# ensearrosage_2.net
KiCad netlist of a schematic drawn in EAGLE
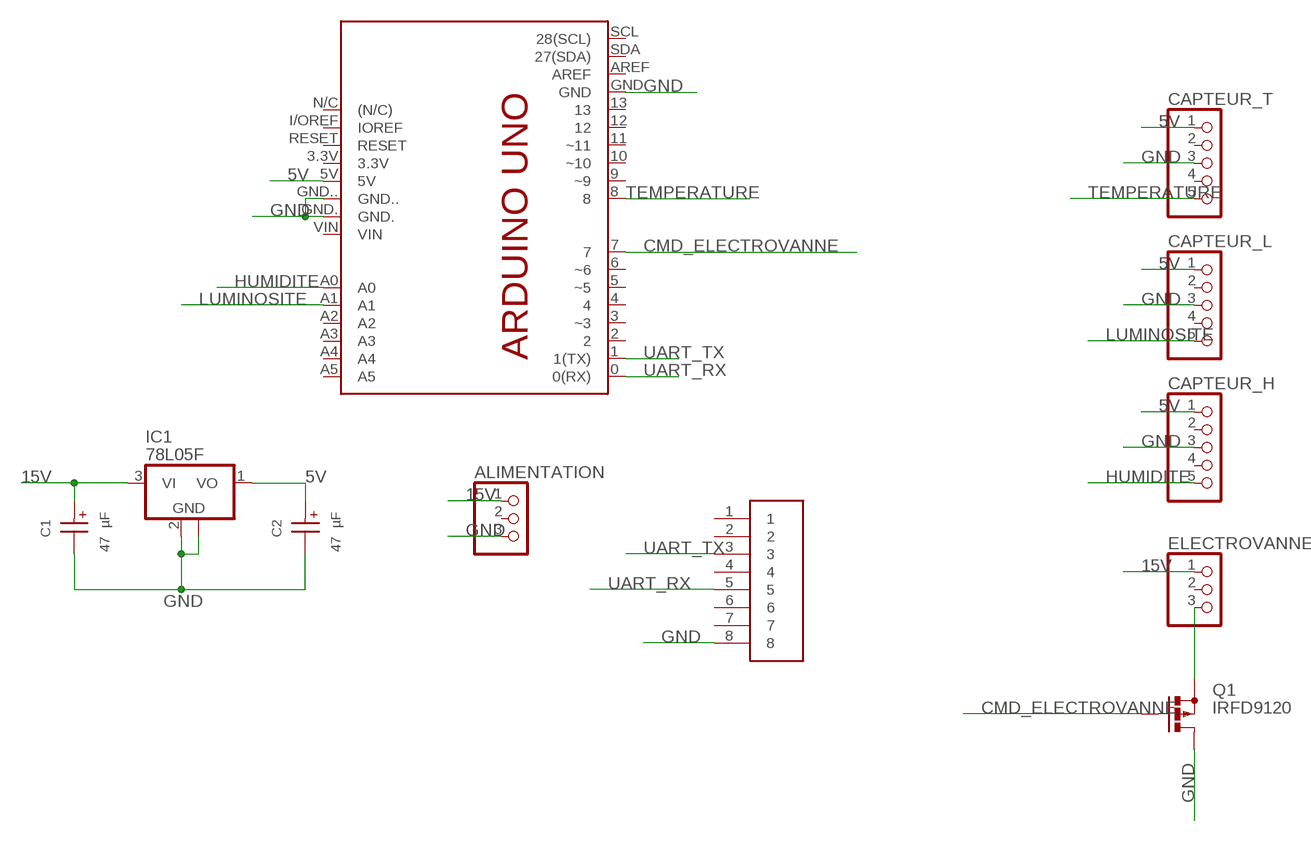
[diagram p0: schematic, sheet 1]

(export (version "E")
  (design (tool "Eeschema 10.0.6"))
  (components
    (comp (ref "ALIMENTATION")
      (value "PINHD-1X3")
      (footprint "eagle-import:1X03")
      (libsource (lib "eagle-import") (part "PINHD-1X3"))
    )
    (comp (ref "C1")
      (value "47 µF")
      (footprint "eagle-import:WCAP-ASLI_5X5.5(DXL)")
      (libsource (lib "eagle-import") (part "WCAP-ASLI_5X5.5_865080342006"))
    )
    (comp (ref "C2")
      (value "47 µF")
      (footprint "eagle-import:WCAP-ASLI_5X5.5(DXL)")
      (libsource (lib "eagle-import") (part "WCAP-ASLI_5X5.5_865080342006"))
    )
    (comp (ref "CAPTEUR_H")
      (value "PINHD-1X5")
      (footprint "eagle-import:1X05")
      (libsource (lib "eagle-import") (part "PINHD-1X5"))
    )
    (comp (ref "CAPTEUR_L")
      (value "PINHD-1X5")
      (footprint "eagle-import:1X05")
      (libsource (lib "eagle-import") (part "PINHD-1X5"))
    )
    (comp (ref "CAPTEUR_T")
      (value "PINHD-1X5")
      (footprint "eagle-import:1X05")
      (libsource (lib "eagle-import") (part "PINHD-1X5"))
    )
    (comp (ref "ELECTROVANNE")
      (value "PINHD-1X3")
      (footprint "eagle-import:1X03")
      (libsource (lib "eagle-import") (part "PINHD-1X3"))
    )
    (comp (ref "IC1")
      (value "78L05F")
      (footprint "eagle-import:SOT89")
      (libsource (lib "eagle-import") (part "78LF05"))
    )
    (comp (ref "PCB1")
      (value "ARDUINO_UNO")
      (footprint "eagle-import:ARDUINO_UNO")
      (libsource (lib "eagle-import") (part "ARDUINO_UNO"))
    )
    (comp (ref "Q1")
      (value "IRFD9120")
      (footprint "eagle-import:C370-01")
      (libsource (lib "eagle-import") (part "IRFD9120"))
    )
    (comp (ref "U$2")
      (value "RJ45")
      (footprint "eagle-import:RJ45")
      (libsource (lib "eagle-import") (part "RJ45"))
    )
  )
  (nets
    (net (code "1") (name "/5V") (class "Default")
      (node (ref "C2") (pin "1") (pinfunction "+_1") (pintype "passive"))
      (node (ref "CAPTEUR_H") (pin "1") (pinfunction "1_1") (pintype "passive"))
      (node (ref "CAPTEUR_L") (pin "1") (pinfunction "1_1") (pintype "passive"))
      (node (ref "CAPTEUR_T") (pin "1") (pinfunction "1_1") (pintype "passive"))
      (node (ref "IC1") (pin "1") (pinfunction "VO_1") (pintype "passive"))
      (node (ref "PCB1") (pin "5V") (pinfunction "5V_5V") (pintype "bidirectional"))
    )
    (net (code "2") (name "/15V") (class "Default")
      (node (ref "ALIMENTATION") (pin "1") (pinfunction "1_1") (pintype "passive"))
      (node (ref "C1") (pin "1") (pinfunction "+_1") (pintype "passive"))
      (node (ref "ELECTROVANNE") (pin "1") (pinfunction "1_1") (pintype "passive"))
      (node (ref "IC1") (pin "3") (pinfunction "VI_3") (pintype "input"))
    )
    (net (code "3") (name "/CMD_ELECTROVANNE") (class "Default")
      (node (ref "PCB1") (pin "7") (pinfunction "7_7") (pintype "bidirectional"))
      (node (ref "Q1") (pin "G") (pinfunction "G_G") (pintype "passive"))
    )
    (net (code "4") (name "/GND") (class "Default")
      (node (ref "ALIMENTATION") (pin "3") (pinfunction "3_3") (pintype "passive"))
      (node (ref "C1") (pin "2") (pinfunction "-_2") (pintype "passive"))
      (node (ref "C2") (pin "2") (pinfunction "-_2") (pintype "passive"))
      (node (ref "CAPTEUR_H") (pin "3") (pinfunction "3_3") (pintype "passive"))
      (node (ref "CAPTEUR_L") (pin "3") (pinfunction "3_3") (pintype "passive"))
      (node (ref "CAPTEUR_T") (pin "3") (pinfunction "3_3") (pintype "passive"))
      (node (ref "IC1") (pin "2") (pinfunction "GND_2") (pintype "passive"))
      (node (ref "IC1") (pin "2@1") (pinfunction "GND_2@1") (pintype "passive"))
      (node (ref "PCB1") (pin "GND") (pinfunction "GND_GND") (pintype "bidirectional"))
      (node (ref "PCB1") (pin "GND.") (pinfunction "GND._GND.") (pintype "bidirectional"))
      (node (ref "PCB1") (pin "GND..") (pinfunction "GND.._GND..") (pintype "bidirectional"))
      (node (ref "Q1") (pin "D") (pinfunction "D_D") (pintype "passive"))
      (node (ref "Q1") (pin "D1") (pinfunction "D_D1") (pintype "passive"))
      (node (ref "U$2") (pin "8") (pinfunction "8_8") (pintype "bidirectional"))
    )
    (net (code "5") (name "/HUMIDITE") (class "Default")
      (node (ref "CAPTEUR_H") (pin "5") (pinfunction "5_5") (pintype "passive"))
      (node (ref "PCB1") (pin "A0") (pinfunction "A0_A0") (pintype "bidirectional"))
    )
    (net (code "6") (name "/LUMINOSITE") (class "Default")
      (node (ref "CAPTEUR_L") (pin "5") (pinfunction "5_5") (pintype "passive"))
      (node (ref "PCB1") (pin "A1") (pinfunction "A1_A1") (pintype "bidirectional"))
    )
    (net (code "7") (name "/TEMPERATURE") (class "Default")
      (node (ref "CAPTEUR_T") (pin "5") (pinfunction "5_5") (pintype "passive"))
      (node (ref "PCB1") (pin "8") (pinfunction "8_8") (pintype "bidirectional"))
    )
    (net (code "8") (name "/UART_RX") (class "Default")
      (node (ref "PCB1") (pin "0") (pinfunction "0(RX)_0") (pintype "bidirectional"))
      (node (ref "U$2") (pin "5") (pinfunction "5_5") (pintype "bidirectional"))
    )
    (net (code "9") (name "/UART_TX") (class "Default")
      (node (ref "PCB1") (pin "1") (pinfunction "1(TX)_1") (pintype "bidirectional"))
      (node (ref "U$2") (pin "3") (pinfunction "3_3") (pintype "bidirectional"))
    )
    (net (code "10") (name "Net-(ELECTROVANNE-Pad3)") (class "Default")
      (node (ref "ELECTROVANNE") (pin "3") (pinfunction "3_3") (pintype "passive"))
      (node (ref "Q1") (pin "S") (pinfunction "S_S") (pintype "passive"))
    )
    (net (code "11") (name "unconnected-(ALIMENTATION-Pad2)") (class "Default")
      (node (ref "ALIMENTATION") (pin "2") (pinfunction "2_2") (pintype "passive"))
    )
    (net (code "12") (name "unconnected-(CAPTEUR_H-Pad2)") (class "Default")
      (node (ref "CAPTEUR_H") (pin "2") (pinfunction "2_2") (pintype "passive"))
    )
    (net (code "13") (name "unconnected-(CAPTEUR_H-Pad4)") (class "Default")
      (node (ref "CAPTEUR_H") (pin "4") (pinfunction "4_4") (pintype "passive"))
    )
    (net (code "14") (name "unconnected-(CAPTEUR_L-Pad2)") (class "Default")
      (node (ref "CAPTEUR_L") (pin "2") (pinfunction "2_2") (pintype "passive"))
    )
    (net (code "15") (name "unconnected-(CAPTEUR_L-Pad4)") (class "Default")
      (node (ref "CAPTEUR_L") (pin "4") (pinfunction "4_4") (pintype "passive"))
    )
    (net (code "16") (name "unconnected-(CAPTEUR_T-Pad2)") (class "Default")
      (node (ref "CAPTEUR_T") (pin "2") (pinfunction "2_2") (pintype "passive"))
    )
    (net (code "17") (name "unconnected-(CAPTEUR_T-Pad4)") (class "Default")
      (node (ref "CAPTEUR_T") (pin "4") (pinfunction "4_4") (pintype "passive"))
    )
    (net (code "18") (name "unconnected-(ELECTROVANNE-Pad2)") (class "Default")
      (node (ref "ELECTROVANNE") (pin "2") (pinfunction "2_2") (pintype "passive"))
    )
    (net (code "19") (name "unconnected-(PCB1-(N{slash}C)-PadN{slash}C)") (class "Default")
      (node (ref "PCB1") (pin "N/C") (pinfunction "(N/C)_N/C") (pintype "bidirectional"))
    )
    (net (code "20") (name "unconnected-(PCB1-27(SDA)-PadSDA)") (class "Default")
      (node (ref "PCB1") (pin "SDA") (pinfunction "27(SDA)_SDA") (pintype "bidirectional"))
    )
    (net (code "21") (name "unconnected-(PCB1-28(SCL)-PadSCL)") (class "Default")
      (node (ref "PCB1") (pin "SCL") (pinfunction "28(SCL)_SCL") (pintype "bidirectional"))
    )
    (net (code "22") (name "unconnected-(PCB1-IOREF-PadI{slash}OREF)") (class "Default")
      (node (ref "PCB1") (pin "I/OREF") (pinfunction "IOREF_I/OREF") (pintype "bidirectional"))
    )
    (net (code "23") (name "unconnected-(PCB1-Pad2)") (class "Default")
      (node (ref "PCB1") (pin "2") (pinfunction "2_2") (pintype "bidirectional"))
    )
    (net (code "24") (name "unconnected-(PCB1-Pad3.3V)") (class "Default")
      (node (ref "PCB1") (pin "3.3V") (pinfunction "3.3V_3.3V") (pintype "bidirectional"))
    )
    (net (code "25") (name "unconnected-(PCB1-Pad4)") (class "Default")
      (node (ref "PCB1") (pin "4") (pinfunction "4_4") (pintype "bidirectional"))
    )
    (net (code "26") (name "unconnected-(PCB1-Pad12)") (class "Default")
      (node (ref "PCB1") (pin "12") (pinfunction "12_12") (pintype "bidirectional"))
    )
    (net (code "27") (name "unconnected-(PCB1-Pad13)") (class "Default")
      (node (ref "PCB1") (pin "13") (pinfunction "13_13") (pintype "bidirectional"))
    )
    (net (code "28") (name "unconnected-(PCB1-PadA2)") (class "Default")
      (node (ref "PCB1") (pin "A2") (pinfunction "A2_A2") (pintype "bidirectional"))
    )
    (net (code "29") (name "unconnected-(PCB1-PadA3)") (class "Default")
      (node (ref "PCB1") (pin "A3") (pinfunction "A3_A3") (pintype "bidirectional"))
    )
    (net (code "30") (name "unconnected-(PCB1-PadA4)") (class "Default")
      (node (ref "PCB1") (pin "A4") (pinfunction "A4_A4") (pintype "bidirectional"))
    )
    (net (code "31") (name "unconnected-(PCB1-PadA5)") (class "Default")
      (node (ref "PCB1") (pin "A5") (pinfunction "A5_A5") (pintype "bidirectional"))
    )
    (net (code "32") (name "unconnected-(PCB1-PadAREF)") (class "Default")
      (node (ref "PCB1") (pin "AREF") (pinfunction "AREF_AREF") (pintype "bidirectional"))
    )
    (net (code "33") (name "unconnected-(PCB1-PadRESET)") (class "Default")
      (node (ref "PCB1") (pin "RESET") (pinfunction "RESET_RESET") (pintype "bidirectional"))
    )
    (net (code "34") (name "unconnected-(PCB1-PadVIN)") (class "Default")
      (node (ref "PCB1") (pin "VIN") (pinfunction "VIN_VIN") (pintype "bidirectional"))
    )
    (net (code "35") (name "unconnected-(PCB1-~{3}-Pad3)") (class "Default")
      (node (ref "PCB1") (pin "3") (pinfunction "~{3}_3") (pintype "bidirectional"))
    )
    (net (code "36") (name "unconnected-(PCB1-~{5}-Pad5)") (class "Default")
      (node (ref "PCB1") (pin "5") (pinfunction "~{5}_5") (pintype "bidirectional"))
    )
    (net (code "37") (name "unconnected-(PCB1-~{6}-Pad6)") (class "Default")
      (node (ref "PCB1") (pin "6") (pinfunction "~{6}_6") (pintype "bidirectional"))
    )
    (net (code "38") (name "unconnected-(PCB1-~{9}-Pad9)") (class "Default")
      (node (ref "PCB1") (pin "9") (pinfunction "~{9}_9") (pintype "bidirectional"))
    )
    (net (code "39") (name "unconnected-(PCB1-~{10}-Pad10)") (class "Default")
      (node (ref "PCB1") (pin "10") (pinfunction "~{10}_10") (pintype "bidirectional"))
    )
    (net (code "40") (name "unconnected-(PCB1-~{11}-Pad11)") (class "Default")
      (node (ref "PCB1") (pin "11") (pinfunction "~{11}_11") (pintype "bidirectional"))
    )
    (net (code "41") (name "unconnected-(U$2-Pad1)") (class "Default")
      (node (ref "U$2") (pin "1") (pinfunction "1_1") (pintype "bidirectional"))
    )
    (net (code "42") (name "unconnected-(U$2-Pad2)") (class "Default")
      (node (ref "U$2") (pin "2") (pinfunction "2_2") (pintype "bidirectional"))
    )
    (net (code "43") (name "unconnected-(U$2-Pad4)") (class "Default")
      (node (ref "U$2") (pin "4") (pinfunction "4_4") (pintype "bidirectional"))
    )
    (net (code "44") (name "unconnected-(U$2-Pad6)") (class "Default")
      (node (ref "U$2") (pin "6") (pinfunction "6_6") (pintype "bidirectional"))
    )
    (net (code "45") (name "unconnected-(U$2-Pad7)") (class "Default")
      (node (ref "U$2") (pin "7") (pinfunction "7_7") (pintype "bidirectional"))
    )
  )
)
